# laser_breakout_board.net
KiCad netlist of a schematic drawn in EasyEDA Pro
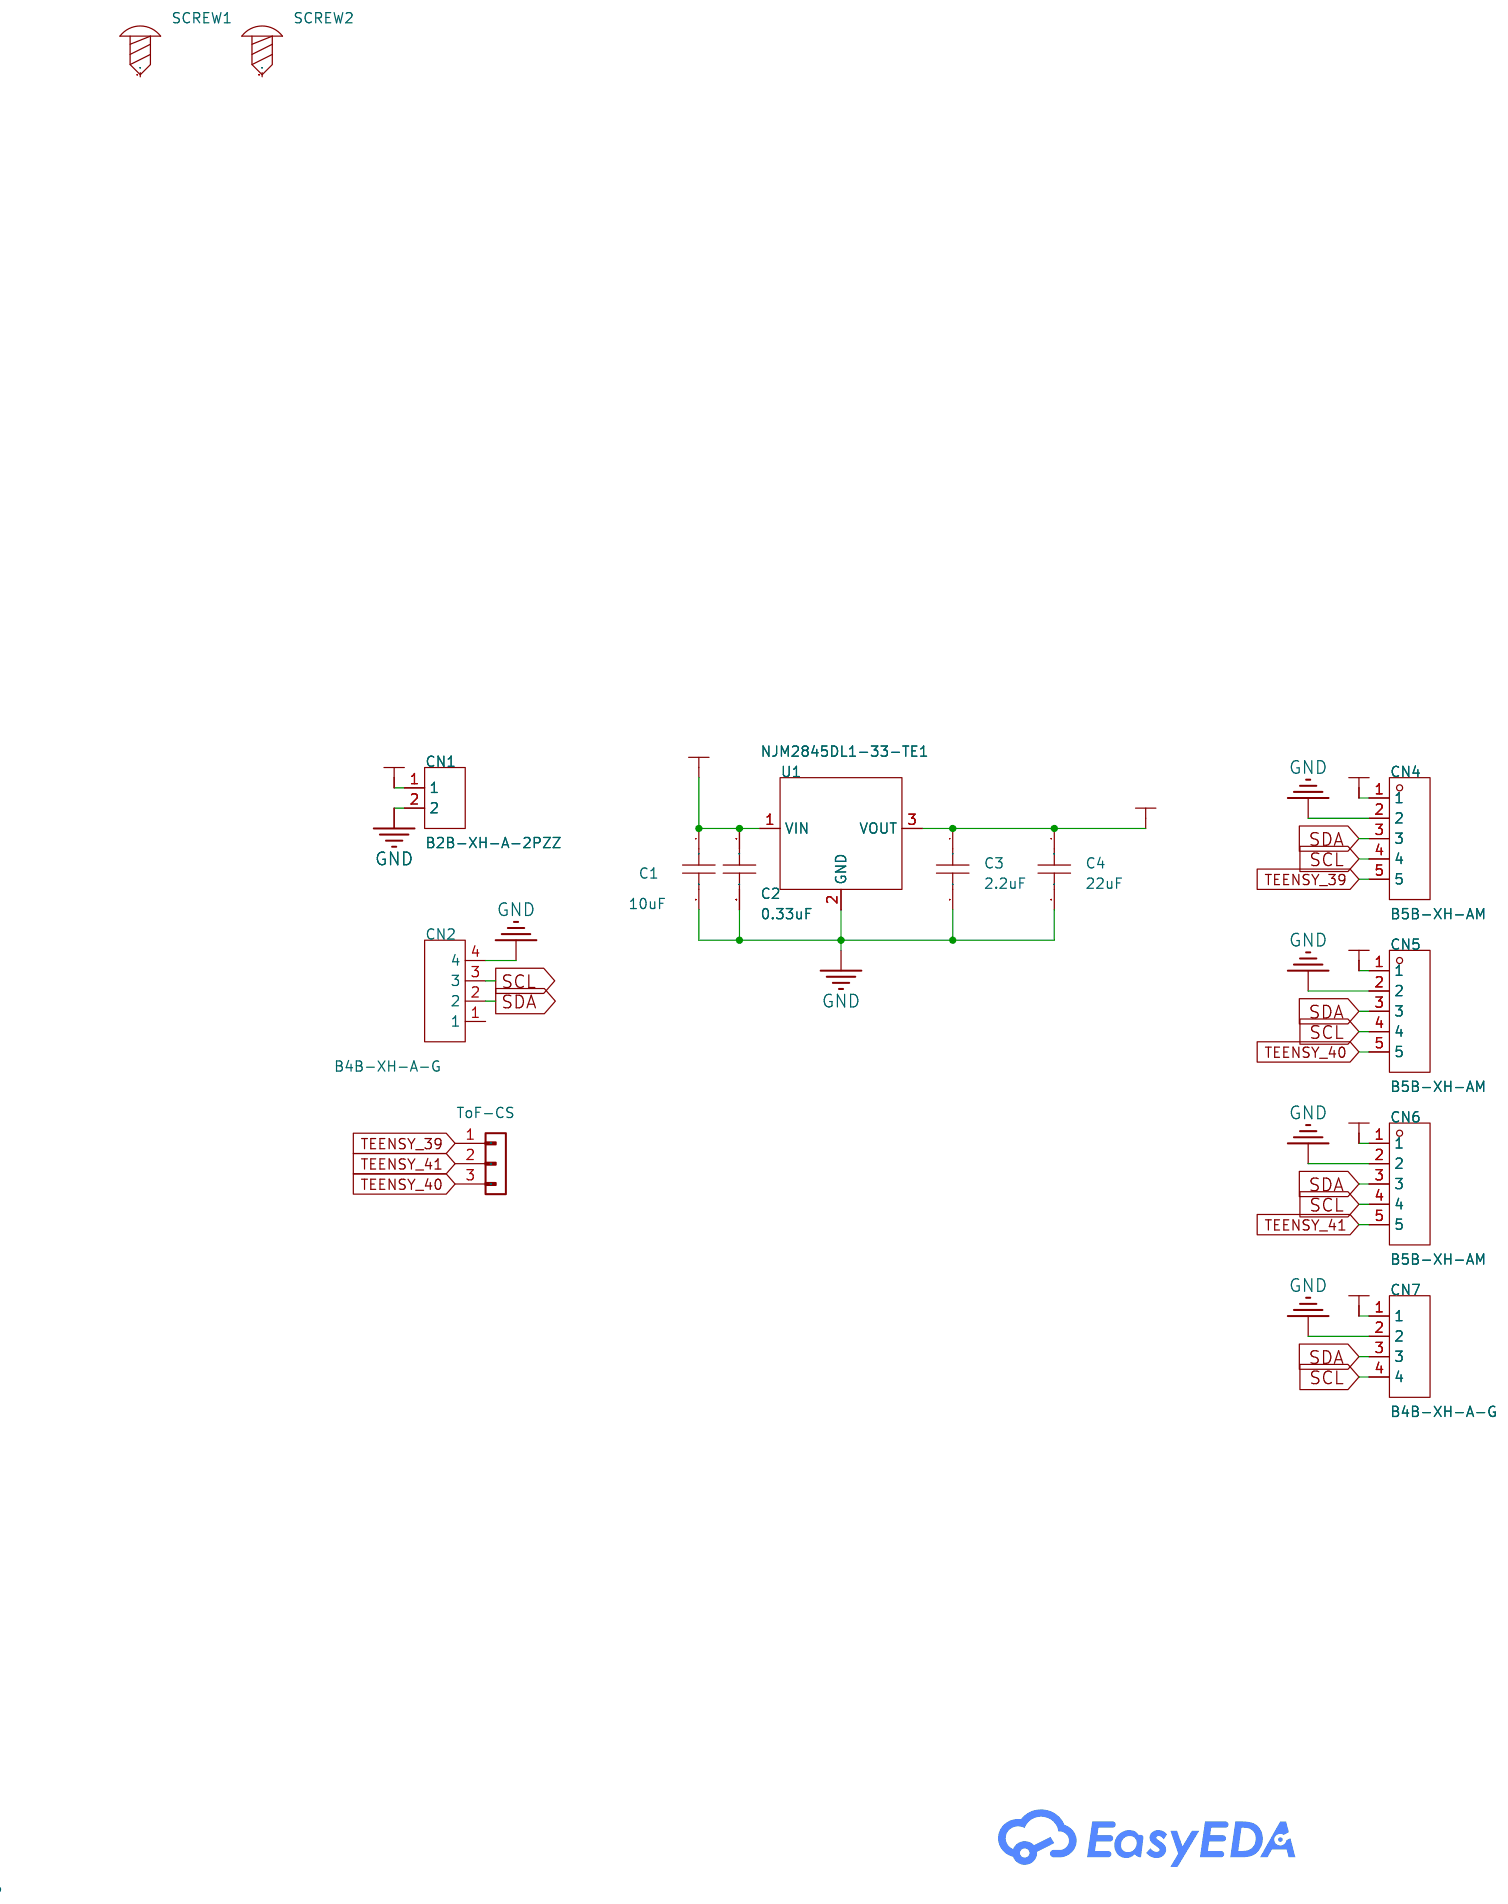
[diagram p0: schematic sheet]

(export (version "E")
  (design (tool "Eeschema 10.0.6"))
  (components
    (comp (ref "C1")
      (value "10uF")
      (footprint "easyedapro:C0603")
      (libsource (lib "easyedapro") (part "CAP"))
    )
    (comp (ref "C2")
      (value "0.33uF")
      (footprint "easyedapro:C0603")
      (libsource (lib "easyedapro") (part "CAP"))
    )
    (comp (ref "C3")
      (value "2.2uF")
      (footprint "easyedapro:C0603")
      (libsource (lib "easyedapro") (part "CAP"))
    )
    (comp (ref "C4")
      (value "22uF")
      (footprint "easyedapro:C0603")
      (libsource (lib "easyedapro") (part "CAP"))
    )
    (comp (ref "CN1")
      (value "B2B-XH-A-2PZZ")
      (footprint "easyedapro:CONN-TH_B2B-XH-A-2PZZ")
      (fields (field (name "Manufacturer") "BXCONN(宝讯)"))
      (libsource (lib "easyedapro") (part "B2B-XH-A-2PZZ"))
    )
    (comp (ref "CN2")
      (value "B4B-XH-A-G")
      (footprint "easyedapro:CONN-TH_B4B-XH-A-G")
      (fields (field (name "Manufacturer") "JST"))
      (libsource (lib "easyedapro") (part "B4B-XH-A-G"))
    )
    (comp (ref "CN3")
      (value "ToF-CS")
      (fields (field (name "Manufacturer Part") "B3B-XH-A(LF)(SN)") (field (name "Manufacturer") "JST"))
      (libsource (lib "easyedapro") (part "Connector_Generic_Conn_01x03"))
    )
    (comp (ref "CN4")
      (value "B5B-XH-AM")
      (footprint "easyedapro:CONN-TH_B5B-XH-AM-LF-SN")
      (fields (field (name "Manufacturer") "JST"))
      (libsource (lib "easyedapro") (part "B5B-XH-AM"))
    )
    (comp (ref "CN5")
      (value "B5B-XH-AM")
      (footprint "easyedapro:CONN-TH_B5B-XH-AM-LF-SN")
      (fields (field (name "Manufacturer") "JST"))
      (libsource (lib "easyedapro") (part "B5B-XH-AM"))
    )
    (comp (ref "CN6")
      (value "B5B-XH-AM")
      (footprint "easyedapro:CONN-TH_B5B-XH-AM-LF-SN")
      (fields (field (name "Manufacturer") "JST"))
      (libsource (lib "easyedapro") (part "B5B-XH-AM"))
    )
    (comp (ref "CN7")
      (value "B4B-XH-A-G")
      (footprint "easyedapro:CONN-TH_B4B-XH-A-G")
      (fields (field (name "Manufacturer") "JST"))
      (libsource (lib "easyedapro") (part "B4B-XH-A-G"))
    )
    (comp (ref "SCREW1")
      (value "~")
      (footprint "easyedapro:Screw-Hole-M2")
      (libsource (lib "easyedapro") (part "Screw-Hole"))
    )
    (comp (ref "SCREW2")
      (value "~")
      (footprint "easyedapro:Screw-Hole-M2")
      (libsource (lib "easyedapro") (part "Screw-Hole"))
    )
    (comp (ref "U1")
      (value "NJM2845DL1-33-TE1")
      (footprint "easyedapro:TO-252-3_L6.6-W6.1-P4.57-LS9.9-BR-CW")
      (fields (field (name "Manufacturer") "Nisshinbo"))
      (libsource (lib "easyedapro") (part "NJM2845DL1-33-TE1"))
    )
  )
  (nets
    (net (code "1") (name "3.3V") (class "Default")
      (node (ref "C3") (pin "1") (pinfunction "1_1") (pintype "input"))
      (node (ref "C4") (pin "1") (pinfunction "1_1") (pintype "input"))
      (node (ref "CN4") (pin "1") (pinfunction "1_1") (pintype "unspecified"))
      (node (ref "CN5") (pin "1") (pinfunction "1_1") (pintype "unspecified"))
      (node (ref "CN6") (pin "1") (pinfunction "1_1") (pintype "unspecified"))
      (node (ref "CN7") (pin "1") (pinfunction "1_1") (pintype "unspecified"))
      (node (ref "U1") (pin "3") (pinfunction "VOUT_3") (pintype "unspecified"))
    )
    (net (code "2") (name "GND") (class "Default")
      (node (ref "C1") (pin "2") (pinfunction "2_2") (pintype "input"))
      (node (ref "C2") (pin "2") (pinfunction "2_2") (pintype "input"))
      (node (ref "C3") (pin "2") (pinfunction "2_2") (pintype "input"))
      (node (ref "C4") (pin "2") (pinfunction "2_2") (pintype "input"))
      (node (ref "CN1") (pin "2") (pinfunction "2_2") (pintype "unspecified"))
      (node (ref "CN2") (pin "4") (pinfunction "4_4") (pintype "unspecified"))
      (node (ref "CN4") (pin "2") (pinfunction "2_2") (pintype "unspecified"))
      (node (ref "CN5") (pin "2") (pinfunction "2_2") (pintype "unspecified"))
      (node (ref "CN6") (pin "2") (pinfunction "2_2") (pintype "unspecified"))
      (node (ref "CN7") (pin "2") (pinfunction "2_2") (pintype "unspecified"))
      (node (ref "U1") (pin "2") (pinfunction "GND_2") (pintype "unspecified"))
    )
    (net (code "3") (name "SCL") (class "Default")
      (node (ref "CN2") (pin "3") (pinfunction "3_3") (pintype "unspecified"))
      (node (ref "CN4") (pin "4") (pinfunction "4_4") (pintype "unspecified"))
      (node (ref "CN5") (pin "4") (pinfunction "4_4") (pintype "unspecified"))
      (node (ref "CN6") (pin "4") (pinfunction "4_4") (pintype "unspecified"))
      (node (ref "CN7") (pin "4") (pinfunction "4_4") (pintype "unspecified"))
    )
    (net (code "4") (name "SDA") (class "Default")
      (node (ref "CN2") (pin "2") (pinfunction "2_2") (pintype "unspecified"))
      (node (ref "CN4") (pin "3") (pinfunction "3_3") (pintype "unspecified"))
      (node (ref "CN5") (pin "3") (pinfunction "3_3") (pintype "unspecified"))
      (node (ref "CN6") (pin "3") (pinfunction "3_3") (pintype "unspecified"))
      (node (ref "CN7") (pin "3") (pinfunction "3_3") (pintype "unspecified"))
    )
    (net (code "5") (name "TEENSY_39") (class "Default")
      (node (ref "CN3") (pin "1") (pinfunction "Pin_1_1") (pintype "unspecified"))
      (node (ref "CN4") (pin "5") (pinfunction "5_5") (pintype "unspecified"))
    )
    (net (code "6") (name "TEENSY_40") (class "Default")
      (node (ref "CN3") (pin "3") (pinfunction "Pin_3_3") (pintype "unspecified"))
      (node (ref "CN5") (pin "5") (pinfunction "5_5") (pintype "unspecified"))
    )
    (net (code "7") (name "TEENSY_41") (class "Default")
      (node (ref "CN3") (pin "2") (pinfunction "Pin_2_2") (pintype "unspecified"))
      (node (ref "CN6") (pin "5") (pinfunction "5_5") (pintype "unspecified"))
    )
    (net (code "8") (name "VIN") (class "Default")
      (node (ref "C1") (pin "1") (pinfunction "1_1") (pintype "input"))
      (node (ref "C2") (pin "1") (pinfunction "1_1") (pintype "input"))
      (node (ref "CN1") (pin "1") (pinfunction "1_1") (pintype "unspecified"))
      (node (ref "U1") (pin "1") (pinfunction "VIN_1") (pintype "unspecified"))
    )
    (net (code "9") (name "unconnected-(CN2-Pad1)") (class "Default")
      (node (ref "CN2") (pin "1") (pinfunction "1_1") (pintype "unspecified"))
    )
    (net (code "10") (name "unconnected-(SCREW1-Pad1)") (class "Default")
      (node (ref "SCREW1") (pin "1") (pinfunction "1_1") (pintype "input"))
    )
    (net (code "11") (name "unconnected-(SCREW2-Pad1)") (class "Default")
      (node (ref "SCREW2") (pin "1") (pinfunction "1_1") (pintype "input"))
    )
  )
)
